# tracker.net
KiCad netlist of a schematic drawn in EAGLE
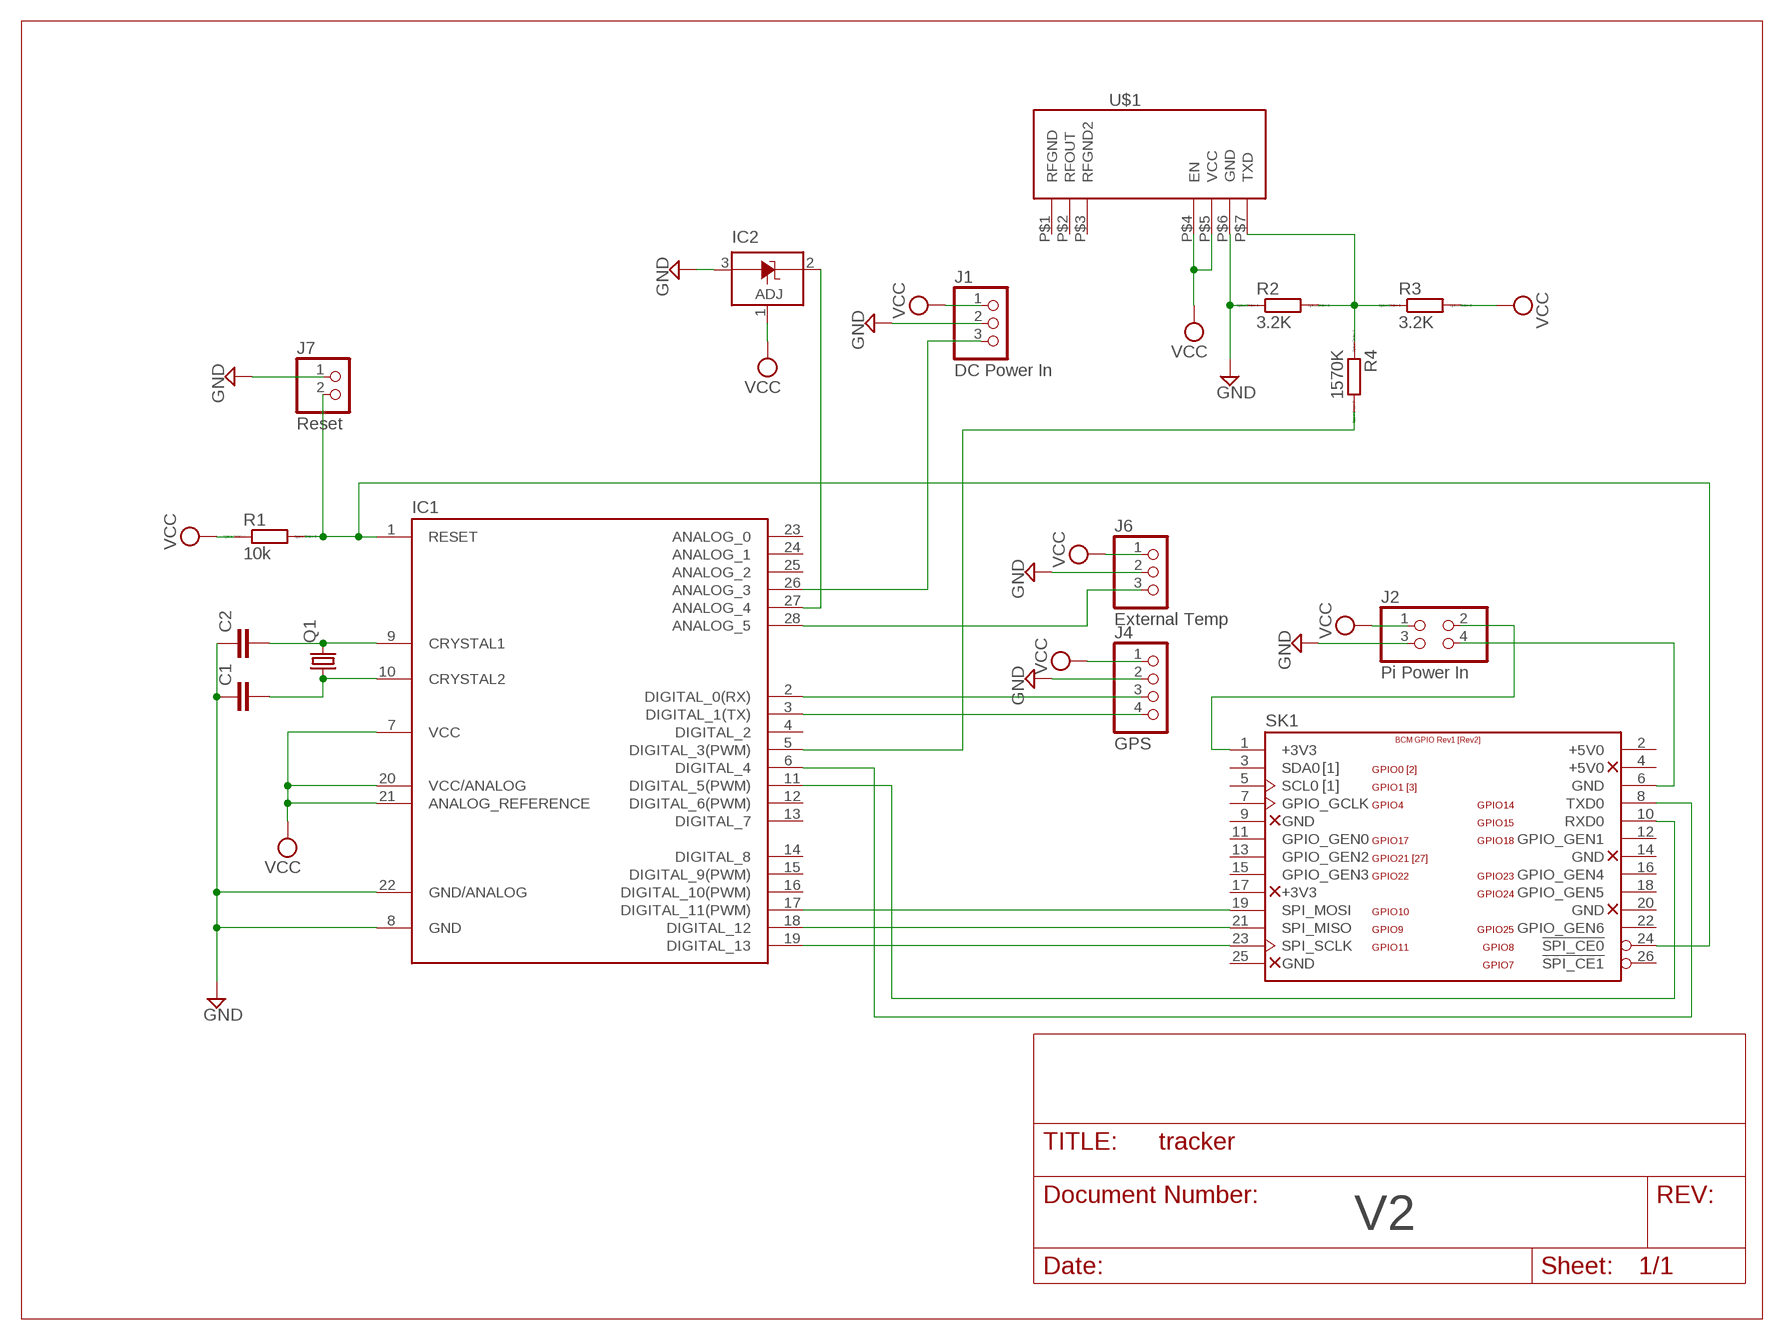
[diagram p0: schematic, sheet 1]

(export (version "E")
  (design (tool "Eeschema 10.0.6"))
  (components
    (comp (ref "C1")
      (value "C-EU025-025X050")
      (footprint "eagle-import:C025-025X050")
      (libsource (lib "eagle-import") (part "C-EU025-025X050"))
    )
    (comp (ref "C2")
      (value "C-EU025-025X050")
      (footprint "eagle-import:C025-025X050")
      (libsource (lib "eagle-import") (part "C-EU025-025X050"))
    )
    (comp (ref "IC1")
      (value "ATMEGA168-PU")
      (footprint "eagle-import:DIL28-3")
      (libsource (lib "eagle-import") (part "ATMEGA168-PU"))
    )
    (comp (ref "IC2")
      (value "LM336LP")
      (footprint "eagle-import:TO92")
      (libsource (lib "eagle-import") (part "LM336LP"))
    )
    (comp (ref "J1")
      (value "DC Power In")
      (footprint "eagle-import:1X03")
      (libsource (lib "eagle-import") (part "PINHD-1X3"))
    )
    (comp (ref "J2")
      (value "Pi Power In")
      (footprint "eagle-import:2X02")
      (libsource (lib "eagle-import") (part "PINHD-2X2"))
    )
    (comp (ref "J4")
      (value "GPS")
      (footprint "eagle-import:1X04")
      (libsource (lib "eagle-import") (part "PINHD-1X4"))
    )
    (comp (ref "J6")
      (value "External Temp")
      (footprint "eagle-import:1X03")
      (libsource (lib "eagle-import") (part "PINHD-1X3"))
    )
    (comp (ref "J7")
      (value "Reset")
      (footprint "eagle-import:1X02")
      (libsource (lib "eagle-import") (part "PINHD-1X2"))
    )
    (comp (ref "Q1")
      (value "CRYSTALHC49S")
      (footprint "eagle-import:HC49_S")
      (libsource (lib "eagle-import") (part "CRYSTALHC49S"))
    )
    (comp (ref "R1")
      (value "10k")
      (footprint "eagle-import:0207_10")
      (libsource (lib "eagle-import") (part "R0207/10"))
    )
    (comp (ref "R2")
      (value "3.2K")
      (footprint "eagle-import:0207_10")
      (libsource (lib "eagle-import") (part "R0207/10"))
    )
    (comp (ref "R3")
      (value "3.2K")
      (footprint "eagle-import:0207_10")
      (libsource (lib "eagle-import") (part "R0207/10"))
    )
    (comp (ref "R4")
      (value "1570K")
      (footprint "eagle-import:0207_10")
      (libsource (lib "eagle-import") (part "R0207/10"))
    )
    (comp (ref "SK1")
      (value "PI-GPIO-PTH")
      (footprint "eagle-import:GPIO-CONNECTOR")
      (libsource (lib "eagle-import") (part "PI-GPIO-PTH"))
    )
    (comp (ref "U$1")
      (value "NTX2")
      (footprint "eagle-import:NTX2")
      (libsource (lib "eagle-import") (part "NTX2"))
    )
  )
  (nets
    (net (code "1") (name "/+5V0") (class "Default")
      (node (ref "SK1") (pin "2") (pinfunction "+5V0_2") (pintype "power_in"))
    )
    (net (code "2") (name "GND") (class "Default")
      (node (ref "C1") (pin "1") (pinfunction "1_1") (pintype "passive"))
      (node (ref "C2") (pin "1") (pinfunction "1_1") (pintype "passive"))
      (node (ref "IC1") (pin "22") (pinfunction "GND/ANALOG_22") (pintype "power_in"))
      (node (ref "IC1") (pin "8") (pinfunction "GND_8") (pintype "power_in"))
      (node (ref "IC2") (pin "3") (pinfunction "A_3") (pintype "input"))
      (node (ref "J1") (pin "2") (pinfunction "2_2") (pintype "passive"))
      (node (ref "J2") (pin "3") (pinfunction "3_3") (pintype "passive"))
      (node (ref "J4") (pin "2") (pinfunction "2_2") (pintype "passive"))
      (node (ref "J6") (pin "2") (pinfunction "2_2") (pintype "passive"))
      (node (ref "J7") (pin "1") (pinfunction "1_1") (pintype "passive"))
      (node (ref "R2") (pin "1") (pinfunction "1_1") (pintype "passive"))
      (node (ref "U$1") (pin "P$6") (pinfunction "GND_P$6") (pintype "power_in"))
    )
    (net (code "3") (name "Net-(IC1-ANALOG_3)") (class "Default")
      (node (ref "IC1") (pin "26") (pinfunction "ANALOG_3_26") (pintype "bidirectional"))
      (node (ref "J1") (pin "3") (pinfunction "3_3") (pintype "passive"))
    )
    (net (code "4") (name "Net-(IC1-ANALOG_4)") (class "Default")
      (node (ref "IC1") (pin "27") (pinfunction "ANALOG_4_27") (pintype "bidirectional"))
      (node (ref "IC2") (pin "2") (pinfunction "C_2") (pintype "passive"))
    )
    (net (code "5") (name "Net-(IC1-ANALOG_5)") (class "Default")
      (node (ref "IC1") (pin "28") (pinfunction "ANALOG_5_28") (pintype "bidirectional"))
      (node (ref "J6") (pin "3") (pinfunction "3_3") (pintype "passive"))
    )
    (net (code "6") (name "Net-(IC1-CRYSTAL1)") (class "Default")
      (node (ref "C2") (pin "2") (pinfunction "2_2") (pintype "passive"))
      (node (ref "IC1") (pin "9") (pinfunction "CRYSTAL1_9") (pintype "bidirectional"))
      (node (ref "Q1") (pin "2") (pinfunction "2_2") (pintype "passive"))
    )
    (net (code "7") (name "Net-(IC1-CRYSTAL2)") (class "Default")
      (node (ref "C1") (pin "2") (pinfunction "2_2") (pintype "passive"))
      (node (ref "IC1") (pin "10") (pinfunction "CRYSTAL2_10") (pintype "bidirectional"))
      (node (ref "Q1") (pin "1") (pinfunction "1_1") (pintype "passive"))
    )
    (net (code "8") (name "Net-(IC1-DIGITAL_0(RX))") (class "Default")
      (node (ref "IC1") (pin "2") (pinfunction "DIGITAL_0(RX)_2") (pintype "bidirectional"))
      (node (ref "J4") (pin "3") (pinfunction "3_3") (pintype "passive"))
    )
    (net (code "9") (name "Net-(IC1-DIGITAL_1(TX))") (class "Default")
      (node (ref "IC1") (pin "3") (pinfunction "DIGITAL_1(TX)_3") (pintype "bidirectional"))
      (node (ref "J4") (pin "4") (pinfunction "4_4") (pintype "passive"))
    )
    (net (code "10") (name "Net-(IC1-DIGITAL_3(PWM))") (class "Default")
      (node (ref "IC1") (pin "5") (pinfunction "DIGITAL_3(PWM)_5") (pintype "bidirectional"))
      (node (ref "R4") (pin "2") (pinfunction "2_2") (pintype "passive"))
    )
    (net (code "11") (name "Net-(IC1-DIGITAL_4)") (class "Default")
      (node (ref "IC1") (pin "6") (pinfunction "DIGITAL_4_6") (pintype "bidirectional"))
      (node (ref "SK1") (pin "8") (pinfunction "TXD0_8") (pintype "bidirectional"))
    )
    (net (code "12") (name "Net-(IC1-DIGITAL_5(PWM))") (class "Default")
      (node (ref "IC1") (pin "11") (pinfunction "DIGITAL_5(PWM)_11") (pintype "bidirectional"))
      (node (ref "SK1") (pin "10") (pinfunction "RXD0_10") (pintype "bidirectional"))
    )
    (net (code "13") (name "Net-(IC1-DIGITAL_11(PWM))") (class "Default")
      (node (ref "IC1") (pin "17") (pinfunction "DIGITAL_11(PWM)_17") (pintype "bidirectional"))
      (node (ref "SK1") (pin "19") (pinfunction "SPI_MOSI_19") (pintype "bidirectional"))
    )
    (net (code "14") (name "Net-(IC1-DIGITAL_12)") (class "Default")
      (node (ref "IC1") (pin "18") (pinfunction "DIGITAL_12_18") (pintype "bidirectional"))
      (node (ref "SK1") (pin "21") (pinfunction "SPI_MISO_21") (pintype "bidirectional"))
    )
    (net (code "15") (name "Net-(IC1-DIGITAL_13)") (class "Default")
      (node (ref "IC1") (pin "19") (pinfunction "DIGITAL_13_19") (pintype "bidirectional"))
      (node (ref "SK1") (pin "23") (pinfunction "SPI_SCLK_23") (pintype "bidirectional"))
    )
    (net (code "16") (name "Net-(IC1-RESET)") (class "Default")
      (node (ref "IC1") (pin "1") (pinfunction "RESET_1") (pintype "bidirectional"))
      (node (ref "J7") (pin "2") (pinfunction "2_2") (pintype "passive"))
      (node (ref "R1") (pin "2") (pinfunction "2_2") (pintype "passive"))
      (node (ref "SK1") (pin "24") (pinfunction "~{SPI_CE0}_24") (pintype "bidirectional"))
    )
    (net (code "17") (name "Net-(SK1-+3V3)") (class "Default")
      (node (ref "J2") (pin "2") (pinfunction "2_2") (pintype "passive"))
      (node (ref "SK1") (pin "1") (pinfunction "+3V3_1") (pintype "power_in"))
    )
    (net (code "18") (name "Net-(SK1-GND)") (class "Default")
      (node (ref "J2") (pin "4") (pinfunction "4_4") (pintype "passive"))
      (node (ref "SK1") (pin "6") (pinfunction "GND_6") (pintype "power_in"))
    )
    (net (code "19") (name "Net-(U$1-TXD)") (class "Default")
      (node (ref "R2") (pin "2") (pinfunction "2_2") (pintype "passive"))
      (node (ref "R3") (pin "1") (pinfunction "1_1") (pintype "passive"))
      (node (ref "R4") (pin "1") (pinfunction "1_1") (pintype "passive"))
      (node (ref "U$1") (pin "P$7") (pinfunction "TXD_P$7") (pintype "input"))
    )
    (net (code "20") (name "VCC") (class "Default")
      (node (ref "IC1") (pin "20") (pinfunction "VCC/ANALOG_20") (pintype "passive"))
      (node (ref "IC1") (pin "21") (pinfunction "ANALOG_REFERENCE_21") (pintype "passive"))
      (node (ref "IC1") (pin "7") (pinfunction "VCC_7") (pintype "power_in"))
      (node (ref "IC2") (pin "1") (pinfunction "ADJ_1") (pintype "input"))
      (node (ref "J1") (pin "1") (pinfunction "1_1") (pintype "passive"))
      (node (ref "J2") (pin "1") (pinfunction "1_1") (pintype "passive"))
      (node (ref "J4") (pin "1") (pinfunction "1_1") (pintype "passive"))
      (node (ref "J6") (pin "1") (pinfunction "1_1") (pintype "passive"))
      (node (ref "R1") (pin "1") (pinfunction "1_1") (pintype "passive"))
      (node (ref "R3") (pin "2") (pinfunction "2_2") (pintype "passive"))
      (node (ref "U$1") (pin "P$4") (pinfunction "EN_P$4") (pintype "bidirectional"))
      (node (ref "U$1") (pin "P$5") (pinfunction "VCC_P$5") (pintype "power_in"))
    )
    (net (code "21") (name "unconnected-(IC1-ANALOG_0-Pad23)") (class "Default")
      (node (ref "IC1") (pin "23") (pinfunction "ANALOG_0_23") (pintype "bidirectional"))
    )
    (net (code "22") (name "unconnected-(IC1-ANALOG_1-Pad24)") (class "Default")
      (node (ref "IC1") (pin "24") (pinfunction "ANALOG_1_24") (pintype "bidirectional"))
    )
    (net (code "23") (name "unconnected-(IC1-ANALOG_2-Pad25)") (class "Default")
      (node (ref "IC1") (pin "25") (pinfunction "ANALOG_2_25") (pintype "bidirectional"))
    )
    (net (code "24") (name "unconnected-(IC1-DIGITAL_2-Pad4)") (class "Default")
      (node (ref "IC1") (pin "4") (pinfunction "DIGITAL_2_4") (pintype "bidirectional"))
    )
    (net (code "25") (name "unconnected-(IC1-DIGITAL_6(PWM)-Pad12)") (class "Default")
      (node (ref "IC1") (pin "12") (pinfunction "DIGITAL_6(PWM)_12") (pintype "bidirectional"))
    )
    (net (code "26") (name "unconnected-(IC1-DIGITAL_7-Pad13)") (class "Default")
      (node (ref "IC1") (pin "13") (pinfunction "DIGITAL_7_13") (pintype "bidirectional"))
    )
    (net (code "27") (name "unconnected-(IC1-DIGITAL_8-Pad14)") (class "Default")
      (node (ref "IC1") (pin "14") (pinfunction "DIGITAL_8_14") (pintype "bidirectional"))
    )
    (net (code "28") (name "unconnected-(IC1-DIGITAL_9(PWM)-Pad15)") (class "Default")
      (node (ref "IC1") (pin "15") (pinfunction "DIGITAL_9(PWM)_15") (pintype "bidirectional"))
    )
    (net (code "29") (name "unconnected-(IC1-DIGITAL_10(PWM)-Pad16)") (class "Default")
      (node (ref "IC1") (pin "16") (pinfunction "DIGITAL_10(PWM)_16") (pintype "bidirectional"))
    )
    (net (code "30") (name "unconnected-(SK1-+3V3-Pad17)") (class "Default")
      (node (ref "SK1") (pin "17") (pinfunction "+3V3_17") (pintype "no_connect"))
    )
    (net (code "31") (name "unconnected-(SK1-+5V0-Pad4)") (class "Default")
      (node (ref "SK1") (pin "4") (pinfunction "+5V0_4") (pintype "no_connect"))
    )
    (net (code "32") (name "unconnected-(SK1-GND-Pad9)") (class "Default")
      (node (ref "SK1") (pin "9") (pinfunction "GND_9") (pintype "no_connect"))
    )
    (net (code "33") (name "unconnected-(SK1-GND-Pad14)") (class "Default")
      (node (ref "SK1") (pin "14") (pinfunction "GND_14") (pintype "no_connect"))
    )
    (net (code "34") (name "unconnected-(SK1-GND-Pad20)") (class "Default")
      (node (ref "SK1") (pin "20") (pinfunction "GND_20") (pintype "no_connect"))
    )
    (net (code "35") (name "unconnected-(SK1-GND-Pad25)") (class "Default")
      (node (ref "SK1") (pin "25") (pinfunction "GND_25") (pintype "no_connect"))
    )
    (net (code "36") (name "unconnected-(SK1-GPIO_GCLK-Pad7)") (class "Default")
      (node (ref "SK1") (pin "7") (pinfunction "GPIO_GCLK_7") (pintype "bidirectional"))
    )
    (net (code "37") (name "unconnected-(SK1-GPIO_GEN0-Pad11)") (class "Default")
      (node (ref "SK1") (pin "11") (pinfunction "GPIO_GEN0_11") (pintype "bidirectional"))
    )
    (net (code "38") (name "unconnected-(SK1-GPIO_GEN1-Pad12)") (class "Default")
      (node (ref "SK1") (pin "12") (pinfunction "GPIO_GEN1_12") (pintype "bidirectional"))
    )
    (net (code "39") (name "unconnected-(SK1-GPIO_GEN2-Pad13)") (class "Default")
      (node (ref "SK1") (pin "13") (pinfunction "GPIO_GEN2_13") (pintype "bidirectional"))
    )
    (net (code "40") (name "unconnected-(SK1-GPIO_GEN3-Pad15)") (class "Default")
      (node (ref "SK1") (pin "15") (pinfunction "GPIO_GEN3_15") (pintype "bidirectional"))
    )
    (net (code "41") (name "unconnected-(SK1-GPIO_GEN4-Pad16)") (class "Default")
      (node (ref "SK1") (pin "16") (pinfunction "GPIO_GEN4_16") (pintype "bidirectional"))
    )
    (net (code "42") (name "unconnected-(SK1-GPIO_GEN5-Pad18)") (class "Default")
      (node (ref "SK1") (pin "18") (pinfunction "GPIO_GEN5_18") (pintype "bidirectional"))
    )
    (net (code "43") (name "unconnected-(SK1-GPIO_GEN6-Pad22)") (class "Default")
      (node (ref "SK1") (pin "22") (pinfunction "GPIO_GEN6_22") (pintype "bidirectional"))
    )
    (net (code "44") (name "unconnected-(SK1-SCL0-Pad5)") (class "Default")
      (node (ref "SK1") (pin "5") (pinfunction "SCL0_5") (pintype "bidirectional"))
    )
    (net (code "45") (name "unconnected-(SK1-SDA0-Pad3)") (class "Default")
      (node (ref "SK1") (pin "3") (pinfunction "SDA0_3") (pintype "bidirectional"))
    )
    (net (code "46") (name "unconnected-(SK1-~{SPI_CE1}-Pad26)") (class "Default")
      (node (ref "SK1") (pin "26") (pinfunction "~{SPI_CE1}_26") (pintype "bidirectional"))
    )
    (net (code "47") (name "unconnected-(U$1-RFGND-PadP$1)") (class "Default")
      (node (ref "U$1") (pin "P$1") (pinfunction "RFGND_P$1") (pintype "no_connect"))
    )
    (net (code "48") (name "unconnected-(U$1-RFGND2-PadP$3)") (class "Default")
      (node (ref "U$1") (pin "P$3") (pinfunction "RFGND2_P$3") (pintype "no_connect"))
    )
    (net (code "49") (name "unconnected-(U$1-RFOUT-PadP$2)") (class "Default")
      (node (ref "U$1") (pin "P$2") (pinfunction "RFOUT_P$2") (pintype "no_connect"))
    )
  )
)
